# Connectors.net
KiCad netlist of a schematic drawn in Altium Designer
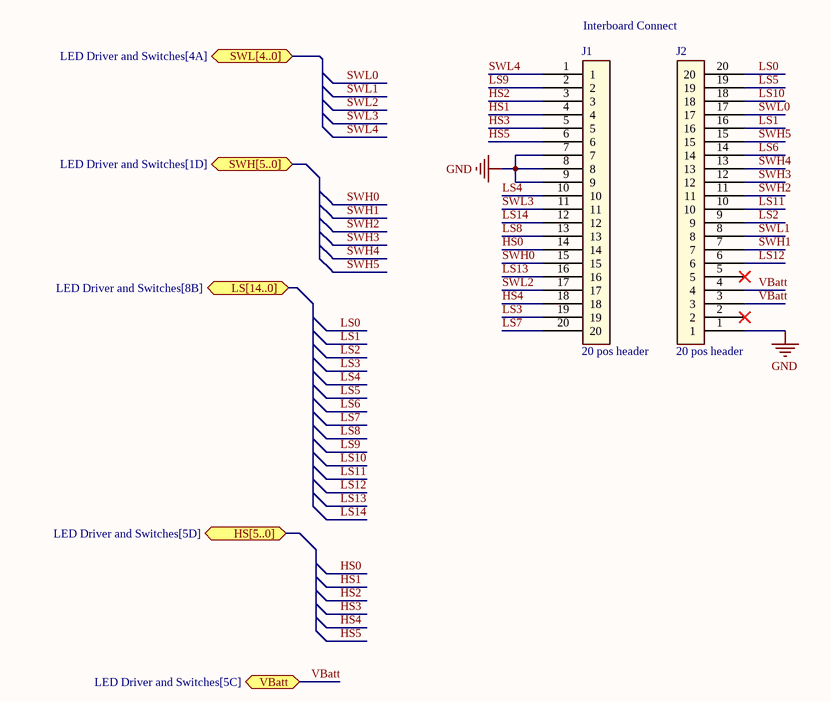
[diagram p0: Connectors.SchDoc]

(export (version "E")
  (design (tool "Eeschema 10.0.6"))
  (components
    (comp (ref "J1")
      (value "20 pos header")
      (footprint "20 pos header")
      (libsource (lib "") (part "20 pos header_1"))
    )
    (comp (ref "J2")
      (value "20 pos header")
      (footprint "20 pos header")
      (libsource (lib "2020-09-26_17-27-19") (part "20 pos header"))
    )
  )
  (nets
    (net (code "1") (name "/HS0") (class "Default")
      (node (ref "J1") (pin "14") (pinfunction "14_14") (pintype "passive"))
    )
    (net (code "2") (name "/HS1") (class "Default")
      (node (ref "J1") (pin "4") (pinfunction "4_4") (pintype "passive"))
    )
    (net (code "3") (name "/HS2") (class "Default")
      (node (ref "J1") (pin "3") (pinfunction "3_3") (pintype "passive"))
    )
    (net (code "4") (name "/HS3") (class "Default")
      (node (ref "J1") (pin "5") (pinfunction "5_5") (pintype "passive"))
    )
    (net (code "5") (name "/HS4") (class "Default")
      (node (ref "J1") (pin "18") (pinfunction "18_18") (pintype "passive"))
    )
    (net (code "6") (name "/HS5") (class "Default")
      (node (ref "J1") (pin "6") (pinfunction "6_6") (pintype "passive"))
    )
    (net (code "8") (name "/LS0") (class "Default")
      (node (ref "J2") (pin "20") (pinfunction "20_20") (pintype "passive"))
    )
    (net (code "9") (name "/LS1") (class "Default")
      (node (ref "J2") (pin "16") (pinfunction "16_16") (pintype "passive"))
    )
    (net (code "10") (name "/LS2") (class "Default")
      (node (ref "J2") (pin "9") (pinfunction "9_9") (pintype "passive"))
    )
    (net (code "11") (name "/LS3") (class "Default")
      (node (ref "J1") (pin "19") (pinfunction "19_19") (pintype "passive"))
    )
    (net (code "12") (name "/LS4") (class "Default")
      (node (ref "J1") (pin "10") (pinfunction "10_10") (pintype "passive"))
    )
    (net (code "13") (name "/LS5") (class "Default")
      (node (ref "J2") (pin "19") (pinfunction "19_19") (pintype "passive"))
    )
    (net (code "14") (name "/LS6") (class "Default")
      (node (ref "J2") (pin "14") (pinfunction "14_14") (pintype "passive"))
    )
    (net (code "15") (name "/LS7") (class "Default")
      (node (ref "J1") (pin "20") (pinfunction "20_20") (pintype "passive"))
    )
    (net (code "16") (name "/LS8") (class "Default")
      (node (ref "J1") (pin "13") (pinfunction "13_13") (pintype "passive"))
    )
    (net (code "17") (name "/LS9") (class "Default")
      (node (ref "J1") (pin "2") (pinfunction "2_2") (pintype "passive"))
    )
    (net (code "18") (name "/LS10") (class "Default")
      (node (ref "J2") (pin "18") (pinfunction "18_18") (pintype "passive"))
    )
    (net (code "19") (name "/LS11") (class "Default")
      (node (ref "J2") (pin "10") (pinfunction "10_10") (pintype "passive"))
    )
    (net (code "20") (name "/LS12") (class "Default")
      (node (ref "J2") (pin "6") (pinfunction "6_6") (pintype "passive"))
    )
    (net (code "21") (name "/LS13") (class "Default")
      (node (ref "J1") (pin "16") (pinfunction "16_16") (pintype "passive"))
    )
    (net (code "22") (name "/LS14") (class "Default")
      (node (ref "J1") (pin "12") (pinfunction "12_12") (pintype "passive"))
    )
    (net (code "24") (name "/SWH0") (class "Default")
      (node (ref "J1") (pin "15") (pinfunction "15_15") (pintype "passive"))
    )
    (net (code "25") (name "/SWH1") (class "Default")
      (node (ref "J2") (pin "7") (pinfunction "7_7") (pintype "passive"))
    )
    (net (code "26") (name "/SWH2") (class "Default")
      (node (ref "J2") (pin "11") (pinfunction "11_11") (pintype "passive"))
    )
    (net (code "27") (name "/SWH3") (class "Default")
      (node (ref "J2") (pin "12") (pinfunction "12_12") (pintype "passive"))
    )
    (net (code "28") (name "/SWH4") (class "Default")
      (node (ref "J2") (pin "13") (pinfunction "13_13") (pintype "passive"))
    )
    (net (code "29") (name "/SWH5") (class "Default")
      (node (ref "J2") (pin "15") (pinfunction "15_15") (pintype "passive"))
    )
    (net (code "31") (name "/SWL0") (class "Default")
      (node (ref "J2") (pin "17") (pinfunction "17_17") (pintype "passive"))
    )
    (net (code "32") (name "/SWL1") (class "Default")
      (node (ref "J2") (pin "8") (pinfunction "8_8") (pintype "passive"))
    )
    (net (code "33") (name "/SWL2") (class "Default")
      (node (ref "J1") (pin "17") (pinfunction "17_17") (pintype "passive"))
    )
    (net (code "34") (name "/SWL3") (class "Default")
      (node (ref "J1") (pin "11") (pinfunction "11_11") (pintype "passive"))
    )
    (net (code "35") (name "/SWL4") (class "Default")
      (node (ref "J1") (pin "1") (pinfunction "1_1") (pintype "passive"))
    )
    (net (code "37") (name "/VBatt") (class "Default")
      (node (ref "J2") (pin "3") (pinfunction "3_3") (pintype "passive"))
      (node (ref "J2") (pin "4") (pinfunction "4_4") (pintype "passive"))
    )
    (net (code "38") (name "GND") (class "Default")
      (node (ref "J1") (pin "7") (pinfunction "7_7") (pintype "passive"))
      (node (ref "J1") (pin "8") (pinfunction "8_8") (pintype "passive"))
      (node (ref "J1") (pin "9") (pinfunction "9_9") (pintype "passive"))
      (node (ref "J2") (pin "1") (pinfunction "1_1") (pintype "passive"))
    )
    (net (code "39") (name "unconnected-(J2-Pad2)") (class "Default")
      (node (ref "J2") (pin "2") (pinfunction "2_2") (pintype "passive+no_connect"))
    )
    (net (code "40") (name "unconnected-(J2-Pad5)") (class "Default")
      (node (ref "J2") (pin "5") (pinfunction "5_5") (pintype "passive+no_connect"))
    )
  )
)
